# MAIN_STACK_V1.net
KiCad netlist of a schematic drawn in EAGLE
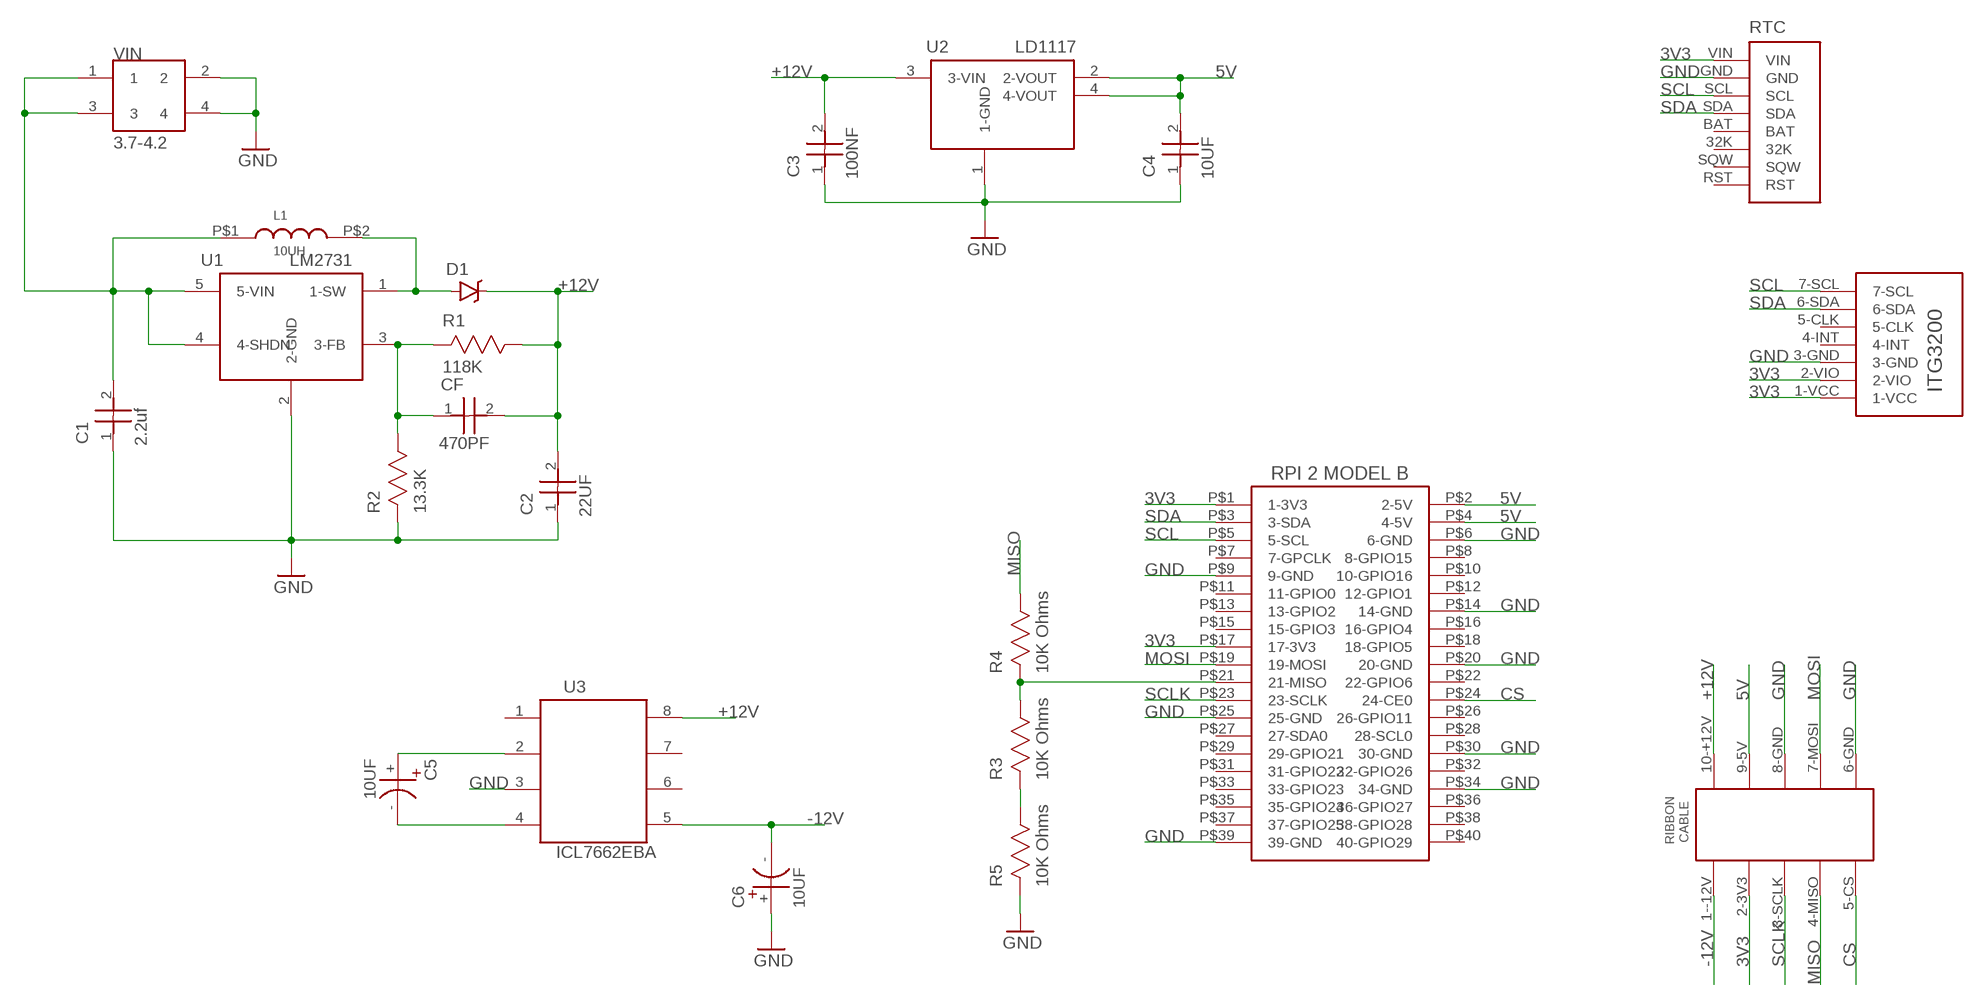
[diagram p0: schematic, sheet 1]

(export (version "E")
  (design (tool "Eeschema 10.0.6"))
  (components
    (comp (ref "C1")
      (value "2.2uf")
      (footprint "eagle-import:CAP1206")
      (fields (field (name "MPN") "C1206C103K5RACTU") (field (name "TOLERANCE") "±10%"))
      (libsource (lib "eagle-import") (part "CAP1206"))
    )
    (comp (ref "C2")
      (value "22UF")
      (footprint "eagle-import:CAP1206")
      (fields (field (name "MPN") "C1206C103K5RACTU") (field (name "TOLERANCE") "±10%"))
      (libsource (lib "eagle-import") (part "CAP1206"))
    )
    (comp (ref "C3")
      (value "100NF")
      (footprint "eagle-import:CAP1206")
      (fields (field (name "MPN") "C1206C103K5RACTU") (field (name "TOLERANCE") "±10%"))
      (libsource (lib "eagle-import") (part "CAP1206"))
    )
    (comp (ref "C4")
      (value "10UF")
      (footprint "eagle-import:CAP1206")
      (fields (field (name "MPN") "C1206C103K5RACTU") (field (name "TOLERANCE") "±10%"))
      (libsource (lib "eagle-import") (part "CAP1206"))
    )
    (comp (ref "C5")
      (value "10UF")
      (footprint "eagle-import:KEMET9BPOLCAP")
      (libsource (lib "eagle-import") (part "POLCAP9B"))
    )
    (comp (ref "C6")
      (value "10UF")
      (footprint "eagle-import:KEMET9BPOLCAP")
      (libsource (lib "eagle-import") (part "POLCAP9B"))
    )
    (comp (ref "CF")
      (value "470PF")
      (footprint "eagle-import:CAP1206")
      (fields (field (name "MPN") "C1206C103K5RACTU") (field (name "TOLERANCE") "±10%"))
      (libsource (lib "eagle-import") (part "CAP1206"))
    )
    (comp (ref "D1")
      (value "DIODE-SCHOTTKY")
      (footprint "eagle-import:SOD-123")
      (libsource (lib "eagle-import") (part "DIODE-SCHOTTKY"))
    )
    (comp (ref "L1")
      (value "10UH")
      (footprint "eagle-import:CDRH125NP")
      (libsource (lib "eagle-import") (part "CDRH125NP"))
    )
    (comp (ref "R1")
      (value "118K")
      (footprint "eagle-import:RES1206")
      (fields (field (name "MPN") "CRCW120610K0FKEA") (field (name "TOLERANCE") "±1%"))
      (libsource (lib "eagle-import") (part "RES1206"))
    )
    (comp (ref "R2")
      (value "13.3K")
      (footprint "eagle-import:RES1206")
      (fields (field (name "MPN") "CRCW120610K0FKEA") (field (name "TOLERANCE") "±1%"))
      (libsource (lib "eagle-import") (part "RES1206"))
    )
    (comp (ref "R3")
      (value "10K Ohms")
      (footprint "eagle-import:RES1206")
      (fields (field (name "MPN") "CRCW120610K0FKEA") (field (name "TOLERANCE") "±1%"))
      (libsource (lib "eagle-import") (part "RES1206"))
    )
    (comp (ref "R4")
      (value "10K Ohms")
      (footprint "eagle-import:RES1206")
      (fields (field (name "MPN") "CRCW120610K0FKEA") (field (name "TOLERANCE") "±1%"))
      (libsource (lib "eagle-import") (part "RES1206"))
    )
    (comp (ref "R5")
      (value "10K Ohms")
      (footprint "eagle-import:RES1206")
      (fields (field (name "MPN") "CRCW120610K0FKEA") (field (name "TOLERANCE") "±1%"))
      (libsource (lib "eagle-import") (part "RES1206"))
    )
    (comp (ref "RTC")
      (value "DS3231BREAKOUT")
      (footprint "eagle-import:DS3231BREAKOUT")
      (libsource (lib "eagle-import") (part "DS3231BREAKOUT"))
    )
    (comp (ref "U$1")
      (value "RPI2")
      (footprint "eagle-import:RPI2")
      (libsource (lib "eagle-import") (part "RPI2"))
    )
    (comp (ref "U$2")
      (value "ITG3200")
      (footprint "eagle-import:ITG3200")
      (libsource (lib "eagle-import") (part "ITG3200"))
    )
    (comp (ref "U$3")
      (value "5X2RIBBONCONNECTOR")
      (footprint "eagle-import:5X2RIBBONCONNECTOR")
      (libsource (lib "eagle-import") (part "5X2RIBBONCONNECTOR"))
    )
    (comp (ref "U1")
      (value "LM2731")
      (footprint "eagle-import:SOT95")
      (libsource (lib "eagle-import") (part "LM2731YMF/NOPB"))
    )
    (comp (ref "U2")
      (value "LD1117")
      (footprint "eagle-import:SOT223")
      (libsource (lib "eagle-import") (part "LD1117"))
    )
    (comp (ref "U3")
      (value "ICL7662EBA")
      (footprint "eagle-import:SOIC8")
      (libsource (lib "eagle-import") (part "ICL7662EBA"))
    )
    (comp (ref "VIN")
      (value "3.7-4.2")
      (footprint "eagle-import:HIROSEPOWERCONNECTOR")
      (libsource (lib "eagle-import") (part "HIROSECONNECTOR"))
    )
  )
  (nets
    (net (code "1") (name "/+12V") (class "Default")
      (node (ref "C2") (pin "2") (pinfunction "P$2_2") (pintype "bidirectional"))
      (node (ref "C3") (pin "2") (pinfunction "P$2_2") (pintype "bidirectional"))
      (node (ref "CF") (pin "2") (pinfunction "P$2_2") (pintype "bidirectional"))
      (node (ref "D1") (pin "C") (pinfunction "C_C") (pintype "passive"))
      (node (ref "R1") (pin "1") (pinfunction "1_1") (pintype "passive"))
      (node (ref "U$3") (pin "10-+12V") (pinfunction "10-+12V_10-+12V") (pintype "bidirectional"))
      (node (ref "U2") (pin "3") (pinfunction "3-VIN_3") (pintype "bidirectional"))
      (node (ref "U3") (pin "8") (pinfunction "8-V+_8") (pintype "bidirectional"))
    )
    (net (code "2") (name "/-12V") (class "Default")
      (node (ref "C6") (pin "-") (pinfunction "-_-") (pintype "bidirectional"))
      (node (ref "U$3") (pin "1--12V") (pinfunction "1--12V_1--12V") (pintype "bidirectional"))
      (node (ref "U3") (pin "5") (pinfunction "5-VOUT_5") (pintype "bidirectional"))
    )
    (net (code "3") (name "/3V3") (class "Default")
      (node (ref "RTC") (pin "VIN") (pinfunction "VIN_VIN") (pintype "bidirectional"))
      (node (ref "U$1") (pin "P$1") (pinfunction "1-3V3_P$1") (pintype "bidirectional"))
      (node (ref "U$1") (pin "P$17") (pinfunction "17-3V3_P$17") (pintype "bidirectional"))
      (node (ref "U$2") (pin "1-VCC") (pinfunction "1-VCC_1-VCC") (pintype "bidirectional"))
      (node (ref "U$2") (pin "2-VIO") (pinfunction "2-VIO_2-VIO") (pintype "bidirectional"))
      (node (ref "U$3") (pin "2-3V3") (pinfunction "2-3V3_2-3V3") (pintype "bidirectional"))
    )
    (net (code "4") (name "/5V") (class "Default")
      (node (ref "C4") (pin "2") (pinfunction "P$2_2") (pintype "bidirectional"))
      (node (ref "U$1") (pin "P$2") (pinfunction "2-5V_P$2") (pintype "bidirectional"))
      (node (ref "U$1") (pin "P$4") (pinfunction "4-5V_P$4") (pintype "bidirectional"))
      (node (ref "U$3") (pin "9-5V") (pinfunction "9-5V_9-5V") (pintype "bidirectional"))
      (node (ref "U2") (pin "2") (pinfunction "2-VOUT_2") (pintype "bidirectional"))
      (node (ref "U2") (pin "4") (pinfunction "4-VOUT_4") (pintype "bidirectional"))
    )
    (net (code "5") (name "/CS") (class "Default")
      (node (ref "U$1") (pin "P$24") (pinfunction "24-CE0_P$24") (pintype "bidirectional"))
      (node (ref "U$3") (pin "5-CS") (pinfunction "5-CS_5-CS") (pintype "bidirectional"))
    )
    (net (code "6") (name "/MISO") (class "Default")
      (node (ref "R4") (pin "1") (pinfunction "1_1") (pintype "passive"))
      (node (ref "U$3") (pin "4-MISO") (pinfunction "4-MISO_4-MISO") (pintype "bidirectional"))
    )
    (net (code "7") (name "/MOSI") (class "Default")
      (node (ref "U$1") (pin "P$19") (pinfunction "19-MOSI_P$19") (pintype "bidirectional"))
      (node (ref "U$3") (pin "7-MOSI") (pinfunction "7-MOSI_7-MOSI") (pintype "bidirectional"))
    )
    (net (code "8") (name "/SCL") (class "Default")
      (node (ref "RTC") (pin "SCL") (pinfunction "SCL_SCL") (pintype "bidirectional"))
      (node (ref "U$1") (pin "P$5") (pinfunction "5-SCL_P$5") (pintype "bidirectional"))
      (node (ref "U$2") (pin "7-SCL") (pinfunction "7-SCL_7-SCL") (pintype "bidirectional"))
    )
    (net (code "9") (name "/SCLK") (class "Default")
      (node (ref "U$1") (pin "P$23") (pinfunction "23-SCLK_P$23") (pintype "bidirectional"))
      (node (ref "U$3") (pin "3-SCLK") (pinfunction "3-SCLK_3-SCLK") (pintype "bidirectional"))
    )
    (net (code "10") (name "/SDA") (class "Default")
      (node (ref "RTC") (pin "SDA") (pinfunction "SDA_SDA") (pintype "bidirectional"))
      (node (ref "U$1") (pin "P$3") (pinfunction "3-SDA_P$3") (pintype "bidirectional"))
      (node (ref "U$2") (pin "6-SDA") (pinfunction "6-SDA_6-SDA") (pintype "bidirectional"))
    )
    (net (code "11") (name "GND") (class "Default")
      (node (ref "C1") (pin "1") (pinfunction "P$1_1") (pintype "bidirectional"))
      (node (ref "C2") (pin "1") (pinfunction "P$1_1") (pintype "bidirectional"))
      (node (ref "C3") (pin "1") (pinfunction "P$1_1") (pintype "bidirectional"))
      (node (ref "C4") (pin "1") (pinfunction "P$1_1") (pintype "bidirectional"))
      (node (ref "C6") (pin "+") (pinfunction "+_+") (pintype "bidirectional"))
      (node (ref "R2") (pin "2") (pinfunction "2_2") (pintype "passive"))
      (node (ref "R5") (pin "2") (pinfunction "2_2") (pintype "passive"))
      (node (ref "RTC") (pin "GND") (pinfunction "GND_GND") (pintype "bidirectional"))
      (node (ref "U$1") (pin "P$14") (pinfunction "14-GND_P$14") (pintype "bidirectional"))
      (node (ref "U$1") (pin "P$20") (pinfunction "20-GND_P$20") (pintype "bidirectional"))
      (node (ref "U$1") (pin "P$25") (pinfunction "25-GND_P$25") (pintype "bidirectional"))
      (node (ref "U$1") (pin "P$30") (pinfunction "30-GND_P$30") (pintype "bidirectional"))
      (node (ref "U$1") (pin "P$34") (pinfunction "34-GND_P$34") (pintype "bidirectional"))
      (node (ref "U$1") (pin "P$39") (pinfunction "39-GND_P$39") (pintype "bidirectional"))
      (node (ref "U$1") (pin "P$6") (pinfunction "6-GND_P$6") (pintype "bidirectional"))
      (node (ref "U$1") (pin "P$9") (pinfunction "9-GND_P$9") (pintype "bidirectional"))
      (node (ref "U$2") (pin "3-GND") (pinfunction "3-GND_3-GND") (pintype "bidirectional"))
      (node (ref "U$3") (pin "6-GND") (pinfunction "6-GND_6-GND") (pintype "bidirectional"))
      (node (ref "U$3") (pin "8-GND") (pinfunction "8-GND_8-GND") (pintype "bidirectional"))
      (node (ref "U1") (pin "2") (pinfunction "2-GND_2") (pintype "bidirectional"))
      (node (ref "U2") (pin "1") (pinfunction "1-GND_1") (pintype "bidirectional"))
      (node (ref "U3") (pin "3") (pinfunction "3-GND_3") (pintype "bidirectional"))
      (node (ref "VIN") (pin "2") (pinfunction "2_2") (pintype "bidirectional"))
      (node (ref "VIN") (pin "4") (pinfunction "4_4") (pintype "bidirectional"))
    )
    (net (code "12") (name "Net-(C1-P$2)") (class "Default")
      (node (ref "C1") (pin "2") (pinfunction "P$2_2") (pintype "bidirectional"))
      (node (ref "L1") (pin "P$1") (pinfunction "1_P$1") (pintype "bidirectional"))
      (node (ref "U1") (pin "4") (pinfunction "4-SHDN_4") (pintype "bidirectional"))
      (node (ref "U1") (pin "5") (pinfunction "5-VIN_5") (pintype "bidirectional"))
      (node (ref "VIN") (pin "1") (pinfunction "1_1") (pintype "bidirectional"))
      (node (ref "VIN") (pin "3") (pinfunction "3_3") (pintype "bidirectional"))
    )
    (net (code "13") (name "Net-(CF-P$1)") (class "Default")
      (node (ref "CF") (pin "1") (pinfunction "P$1_1") (pintype "bidirectional"))
      (node (ref "R1") (pin "2") (pinfunction "2_2") (pintype "passive"))
      (node (ref "R2") (pin "1") (pinfunction "1_1") (pintype "passive"))
      (node (ref "U1") (pin "3") (pinfunction "3-FB_3") (pintype "bidirectional"))
    )
    (net (code "14") (name "Net-(L1-2)") (class "Default")
      (node (ref "D1") (pin "A") (pinfunction "A_A") (pintype "passive"))
      (node (ref "L1") (pin "P$2") (pinfunction "2_P$2") (pintype "bidirectional"))
      (node (ref "U1") (pin "1") (pinfunction "1-SW_1") (pintype "bidirectional"))
    )
    (net (code "15") (name "Net-(R3-Pad2)") (class "Default")
      (node (ref "R3") (pin "2") (pinfunction "2_2") (pintype "passive"))
      (node (ref "R5") (pin "1") (pinfunction "1_1") (pintype "passive"))
    )
    (net (code "16") (name "Net-(U$1-21-MISO)") (class "Default")
      (node (ref "R3") (pin "1") (pinfunction "1_1") (pintype "passive"))
      (node (ref "R4") (pin "2") (pinfunction "2_2") (pintype "passive"))
      (node (ref "U$1") (pin "P$21") (pinfunction "21-MISO_P$21") (pintype "bidirectional"))
    )
    (net (code "17") (name "Net-(U3-2-CAP+)") (class "Default")
      (node (ref "C5") (pin "+") (pinfunction "+_+") (pintype "bidirectional"))
      (node (ref "U3") (pin "2") (pinfunction "2-CAP+_2") (pintype "bidirectional"))
    )
    (net (code "18") (name "Net-(U3-4-CAP-)") (class "Default")
      (node (ref "C5") (pin "-") (pinfunction "-_-") (pintype "bidirectional"))
      (node (ref "U3") (pin "4") (pinfunction "4-CAP-_4") (pintype "bidirectional"))
    )
    (net (code "19") (name "unconnected-(RTC-Pad32K)") (class "Default")
      (node (ref "RTC") (pin "32K") (pinfunction "32K_32K") (pintype "bidirectional"))
    )
    (net (code "20") (name "unconnected-(RTC-PadBAT)") (class "Default")
      (node (ref "RTC") (pin "BAT") (pinfunction "BAT_BAT") (pintype "bidirectional"))
    )
    (net (code "21") (name "unconnected-(RTC-PadRST)") (class "Default")
      (node (ref "RTC") (pin "RST") (pinfunction "RST_RST") (pintype "bidirectional"))
    )
    (net (code "22") (name "unconnected-(RTC-PadSQW)") (class "Default")
      (node (ref "RTC") (pin "SQW") (pinfunction "SQW_SQW") (pintype "bidirectional"))
    )
    (net (code "23") (name "unconnected-(U$1-7-GPCLK-PadP$7)") (class "Default")
      (node (ref "U$1") (pin "P$7") (pinfunction "7-GPCLK_P$7") (pintype "bidirectional"))
    )
    (net (code "24") (name "unconnected-(U$1-8-GPIO15-PadP$8)") (class "Default")
      (node (ref "U$1") (pin "P$8") (pinfunction "8-GPIO15_P$8") (pintype "bidirectional"))
    )
    (net (code "25") (name "unconnected-(U$1-10-GPIO16-PadP$10)") (class "Default")
      (node (ref "U$1") (pin "P$10") (pinfunction "10-GPIO16_P$10") (pintype "bidirectional"))
    )
    (net (code "26") (name "unconnected-(U$1-11-GPIO0-PadP$11)") (class "Default")
      (node (ref "U$1") (pin "P$11") (pinfunction "11-GPIO0_P$11") (pintype "bidirectional"))
    )
    (net (code "27") (name "unconnected-(U$1-12-GPIO1-PadP$12)") (class "Default")
      (node (ref "U$1") (pin "P$12") (pinfunction "12-GPIO1_P$12") (pintype "bidirectional"))
    )
    (net (code "28") (name "unconnected-(U$1-13-GPIO2-PadP$13)") (class "Default")
      (node (ref "U$1") (pin "P$13") (pinfunction "13-GPIO2_P$13") (pintype "bidirectional"))
    )
    (net (code "29") (name "unconnected-(U$1-15-GPIO3-PadP$15)") (class "Default")
      (node (ref "U$1") (pin "P$15") (pinfunction "15-GPIO3_P$15") (pintype "bidirectional"))
    )
    (net (code "30") (name "unconnected-(U$1-16-GPIO4-PadP$16)") (class "Default")
      (node (ref "U$1") (pin "P$16") (pinfunction "16-GPIO4_P$16") (pintype "bidirectional"))
    )
    (net (code "31") (name "unconnected-(U$1-18-GPIO5-PadP$18)") (class "Default")
      (node (ref "U$1") (pin "P$18") (pinfunction "18-GPIO5_P$18") (pintype "bidirectional"))
    )
    (net (code "32") (name "unconnected-(U$1-22-GPIO6-PadP$22)") (class "Default")
      (node (ref "U$1") (pin "P$22") (pinfunction "22-GPIO6_P$22") (pintype "bidirectional"))
    )
    (net (code "33") (name "unconnected-(U$1-26-GPIO11-PadP$26)") (class "Default")
      (node (ref "U$1") (pin "P$26") (pinfunction "26-GPIO11_P$26") (pintype "bidirectional"))
    )
    (net (code "34") (name "unconnected-(U$1-27-SDA0-PadP$27)") (class "Default")
      (node (ref "U$1") (pin "P$27") (pinfunction "27-SDA0_P$27") (pintype "bidirectional"))
    )
    (net (code "35") (name "unconnected-(U$1-28-SCL0-PadP$28)") (class "Default")
      (node (ref "U$1") (pin "P$28") (pinfunction "28-SCL0_P$28") (pintype "bidirectional"))
    )
    (net (code "36") (name "unconnected-(U$1-29-GPIO21-PadP$29)") (class "Default")
      (node (ref "U$1") (pin "P$29") (pinfunction "29-GPIO21_P$29") (pintype "bidirectional"))
    )
    (net (code "37") (name "unconnected-(U$1-31-GPIO22-PadP$31)") (class "Default")
      (node (ref "U$1") (pin "P$31") (pinfunction "31-GPIO22_P$31") (pintype "bidirectional"))
    )
    (net (code "38") (name "unconnected-(U$1-32-GPIO26-PadP$32)") (class "Default")
      (node (ref "U$1") (pin "P$32") (pinfunction "32-GPIO26_P$32") (pintype "bidirectional"))
    )
    (net (code "39") (name "unconnected-(U$1-33-GPIO23-PadP$33)") (class "Default")
      (node (ref "U$1") (pin "P$33") (pinfunction "33-GPIO23_P$33") (pintype "bidirectional"))
    )
    (net (code "40") (name "unconnected-(U$1-35-GPIO24-PadP$35)") (class "Default")
      (node (ref "U$1") (pin "P$35") (pinfunction "35-GPIO24_P$35") (pintype "bidirectional"))
    )
    (net (code "41") (name "unconnected-(U$1-36-GPIO27-PadP$36)") (class "Default")
      (node (ref "U$1") (pin "P$36") (pinfunction "36-GPIO27_P$36") (pintype "bidirectional"))
    )
    (net (code "42") (name "unconnected-(U$1-37-GPIO25-PadP$37)") (class "Default")
      (node (ref "U$1") (pin "P$37") (pinfunction "37-GPIO25_P$37") (pintype "bidirectional"))
    )
    (net (code "43") (name "unconnected-(U$1-38-GPIO28-PadP$38)") (class "Default")
      (node (ref "U$1") (pin "P$38") (pinfunction "38-GPIO28_P$38") (pintype "bidirectional"))
    )
    (net (code "44") (name "unconnected-(U$1-40-GPIO29-PadP$40)") (class "Default")
      (node (ref "U$1") (pin "P$40") (pinfunction "40-GPIO29_P$40") (pintype "bidirectional"))
    )
    (net (code "45") (name "unconnected-(U$2-Pad4-INT)") (class "Default")
      (node (ref "U$2") (pin "4-INT") (pinfunction "4-INT_4-INT") (pintype "bidirectional"))
    )
    (net (code "46") (name "unconnected-(U$2-Pad5-CLK)") (class "Default")
      (node (ref "U$2") (pin "5-CLK") (pinfunction "5-CLK_5-CLK") (pintype "bidirectional"))
    )
    (net (code "47") (name "unconnected-(U3-1-TEST-Pad1)") (class "Default")
      (node (ref "U3") (pin "1") (pinfunction "1-TEST_1") (pintype "bidirectional"))
    )
    (net (code "48") (name "unconnected-(U3-6-LV-Pad6)") (class "Default")
      (node (ref "U3") (pin "6") (pinfunction "6-LV_6") (pintype "bidirectional"))
    )
    (net (code "49") (name "unconnected-(U3-7-OSC-Pad7)") (class "Default")
      (node (ref "U3") (pin "7") (pinfunction "7-OSC_7") (pintype "bidirectional"))
    )
  )
)
